# esp32-controller.net
KiCad netlist of a schematic drawn in EAGLE
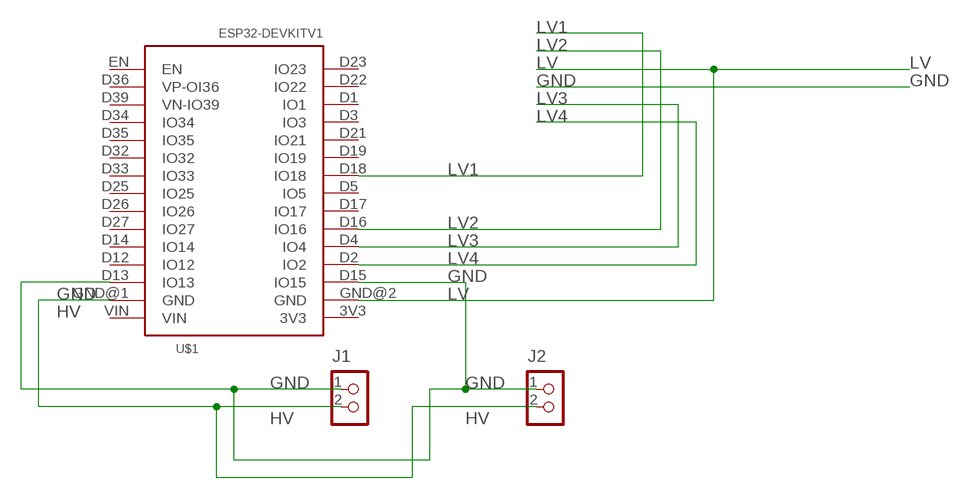
[diagram p0: schematic, sheet 1]

(export (version "E")
  (design (tool "Eeschema 10.0.6"))
  (components
    (comp (ref "J1")
      (value "CON_TERMINAL_BLOCK_02-5MM")
      (footprint "eagle-import:TERMINAL_BLOCK_2P_5")
      (libsource (lib "eagle-import") (part "CON_TERMINAL_BLOCK_02-5MM"))
    )
    (comp (ref "J2")
      (value "CON_TERMINAL_BLOCK_02-5MM")
      (footprint "eagle-import:TERMINAL_BLOCK_2P_5")
      (libsource (lib "eagle-import") (part "CON_TERMINAL_BLOCK_02-5MM"))
    )
    (comp (ref "U$1")
      (value "ESP32DEVKITV1")
      (footprint "eagle-import:ESP32-DEVKITV1")
      (libsource (lib "eagle-import") (part "ESP32DEVKITV1"))
    )
  )
  (nets
    (net (code "1") (name "/GND") (class "Default")
      (node (ref "J1") (pin "1") (pinfunction "1_1") (pintype "passive"))
      (node (ref "J2") (pin "1") (pinfunction "1_1") (pintype "passive"))
      (node (ref "U$1") (pin "D13") (pinfunction "IO13_D13") (pintype "bidirectional"))
      (node (ref "U$1") (pin "D15") (pinfunction "IO15_D15") (pintype "bidirectional"))
    )
    (net (code "2") (name "/HV") (class "Default")
      (node (ref "J1") (pin "2") (pinfunction "2_2") (pintype "passive"))
      (node (ref "J2") (pin "2") (pinfunction "2_2") (pintype "passive"))
      (node (ref "U$1") (pin "GND@1") (pinfunction "GND_GND@1") (pintype "bidirectional"))
    )
    (net (code "3") (name "/LV") (class "Default")
      (node (ref "U$1") (pin "GND@2") (pinfunction "GND_GND@2") (pintype "bidirectional"))
    )
    (net (code "4") (name "/LV1") (class "Default")
      (node (ref "U$1") (pin "D18") (pinfunction "IO18_D18") (pintype "bidirectional"))
    )
    (net (code "5") (name "/LV2") (class "Default")
      (node (ref "U$1") (pin "D16") (pinfunction "IO16_D16") (pintype "bidirectional"))
    )
    (net (code "6") (name "/LV3") (class "Default")
      (node (ref "U$1") (pin "D4") (pinfunction "IO4_D4") (pintype "bidirectional"))
    )
    (net (code "7") (name "/LV4") (class "Default")
      (node (ref "U$1") (pin "D2") (pinfunction "IO2_D2") (pintype "bidirectional"))
    )
    (net (code "8") (name "unconnected-(U$1-IO1-PadD1)") (class "Default")
      (node (ref "U$1") (pin "D1") (pinfunction "IO1_D1") (pintype "bidirectional"))
    )
    (net (code "9") (name "unconnected-(U$1-IO3-PadD3)") (class "Default")
      (node (ref "U$1") (pin "D3") (pinfunction "IO3_D3") (pintype "bidirectional"))
    )
    (net (code "10") (name "unconnected-(U$1-IO5-PadD5)") (class "Default")
      (node (ref "U$1") (pin "D5") (pinfunction "IO5_D5") (pintype "bidirectional"))
    )
    (net (code "11") (name "unconnected-(U$1-IO12-PadD12)") (class "Default")
      (node (ref "U$1") (pin "D12") (pinfunction "IO12_D12") (pintype "bidirectional"))
    )
    (net (code "12") (name "unconnected-(U$1-IO14-PadD14)") (class "Default")
      (node (ref "U$1") (pin "D14") (pinfunction "IO14_D14") (pintype "bidirectional"))
    )
    (net (code "13") (name "unconnected-(U$1-IO17-PadD17)") (class "Default")
      (node (ref "U$1") (pin "D17") (pinfunction "IO17_D17") (pintype "bidirectional"))
    )
    (net (code "14") (name "unconnected-(U$1-IO19-PadD19)") (class "Default")
      (node (ref "U$1") (pin "D19") (pinfunction "IO19_D19") (pintype "bidirectional"))
    )
    (net (code "15") (name "unconnected-(U$1-IO21-PadD21)") (class "Default")
      (node (ref "U$1") (pin "D21") (pinfunction "IO21_D21") (pintype "bidirectional"))
    )
    (net (code "16") (name "unconnected-(U$1-IO22-PadD22)") (class "Default")
      (node (ref "U$1") (pin "D22") (pinfunction "IO22_D22") (pintype "bidirectional"))
    )
    (net (code "17") (name "unconnected-(U$1-IO23-PadD23)") (class "Default")
      (node (ref "U$1") (pin "D23") (pinfunction "IO23_D23") (pintype "bidirectional"))
    )
    (net (code "18") (name "unconnected-(U$1-IO25-PadD25)") (class "Default")
      (node (ref "U$1") (pin "D25") (pinfunction "IO25_D25") (pintype "bidirectional"))
    )
    (net (code "19") (name "unconnected-(U$1-IO26-PadD26)") (class "Default")
      (node (ref "U$1") (pin "D26") (pinfunction "IO26_D26") (pintype "bidirectional"))
    )
    (net (code "20") (name "unconnected-(U$1-IO27-PadD27)") (class "Default")
      (node (ref "U$1") (pin "D27") (pinfunction "IO27_D27") (pintype "bidirectional"))
    )
    (net (code "21") (name "unconnected-(U$1-IO32-PadD32)") (class "Default")
      (node (ref "U$1") (pin "D32") (pinfunction "IO32_D32") (pintype "bidirectional"))
    )
    (net (code "22") (name "unconnected-(U$1-IO33-PadD33)") (class "Default")
      (node (ref "U$1") (pin "D33") (pinfunction "IO33_D33") (pintype "bidirectional"))
    )
    (net (code "23") (name "unconnected-(U$1-IO34-PadD34)") (class "Default")
      (node (ref "U$1") (pin "D34") (pinfunction "IO34_D34") (pintype "bidirectional"))
    )
    (net (code "24") (name "unconnected-(U$1-IO35-PadD35)") (class "Default")
      (node (ref "U$1") (pin "D35") (pinfunction "IO35_D35") (pintype "bidirectional"))
    )
    (net (code "25") (name "unconnected-(U$1-Pad3V3)") (class "Default")
      (node (ref "U$1") (pin "3V3") (pinfunction "3V3_3V3") (pintype "bidirectional"))
    )
    (net (code "26") (name "unconnected-(U$1-PadEN)") (class "Default")
      (node (ref "U$1") (pin "EN") (pinfunction "EN_EN") (pintype "bidirectional"))
    )
    (net (code "27") (name "unconnected-(U$1-PadVIN)") (class "Default")
      (node (ref "U$1") (pin "VIN") (pinfunction "VIN_VIN") (pintype "bidirectional"))
    )
    (net (code "28") (name "unconnected-(U$1-VN-IO39-PadD39)") (class "Default")
      (node (ref "U$1") (pin "D39") (pinfunction "VN-IO39_D39") (pintype "bidirectional"))
    )
    (net (code "29") (name "unconnected-(U$1-VP-OI36-PadD36)") (class "Default")
      (node (ref "U$1") (pin "D36") (pinfunction "VP-OI36_D36") (pintype "bidirectional"))
    )
  )
)
